# ETHERNET.net
KiCad netlist of a schematic drawn in Altium Designer
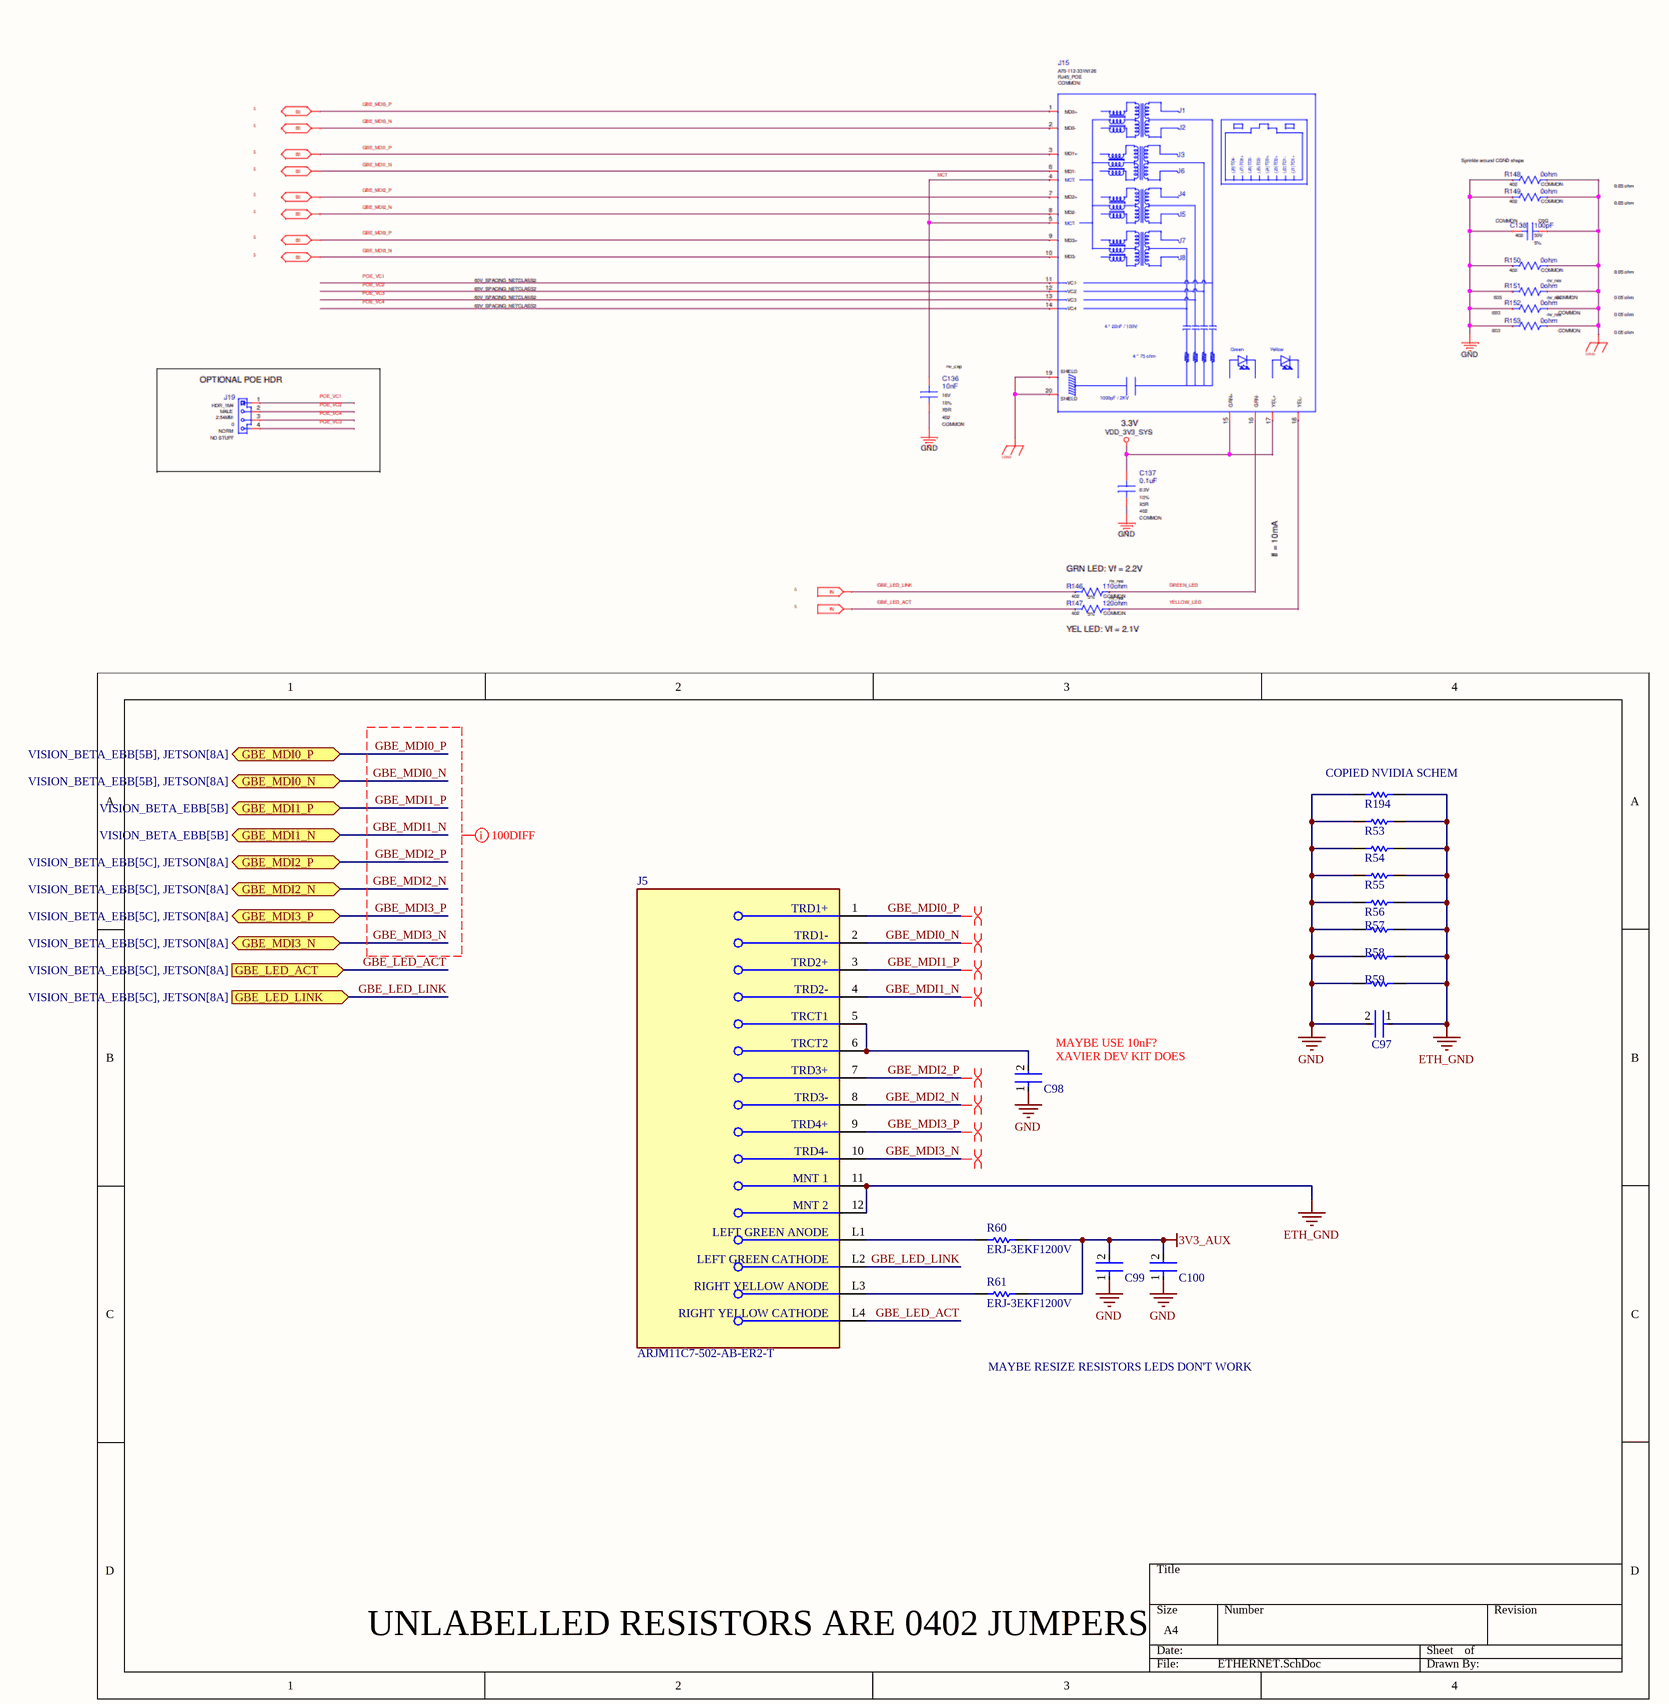
[diagram p0: ETHERNET.SchDoc]

(export (version "E")
  (design (tool "Eeschema 10.0.6"))
  (components
    (comp (ref "C97")
      (value "C1005X7R1H104K050BB")
      (footprint "FP-C1005-050-0_05-IPC_C")
      (description "Multilayer Ceramic Capacitors 100nF ±10% 50V X7R SMD 0402")
      (fields (field (name "VOLTAGE") "50V") (field (name "TOLERANCE") "10%"))
      (libsource (lib "Altium Content Vault") (part "b4654b650e69147ec39a6b967a45e02"))
    )
    (comp (ref "C98")
      (value "C1005X7R1H104K050BB")
      (footprint "FP-C1005-050-0_05-IPC_C")
      (description "Multilayer Ceramic Capacitors 100nF ±10% 50V X7R SMD 0402")
      (fields (field (name "VOLTAGE") "50V") (field (name "TOLERANCE") "10%"))
      (libsource (lib "Altium Content Vault") (part "b4654b650e69147ec39a6b967a45e02"))
    )
    (comp (ref "C99")
      (value "C1005X7R1H104K050BB")
      (footprint "FP-C1005-050-0_05-IPC_C")
      (description "Multilayer Ceramic Capacitors 100nF ±10% 50V X7R SMD 0402")
      (fields (field (name "VOLTAGE") "50V") (field (name "TOLERANCE") "10%"))
      (libsource (lib "Altium Content Vault") (part "b4654b650e69147ec39a6b967a45e02"))
    )
    (comp (ref "C100")
      (value "C1005X7R1H104K050BB")
      (footprint "FP-C1005-050-0_05-IPC_C")
      (description "Multilayer Ceramic Capacitors 100nF ±10% 50V X7R SMD 0402")
      (fields (field (name "VOLTAGE") "50V") (field (name "TOLERANCE") "10%"))
      (libsource (lib "Altium Content Vault") (part "b4654b650e69147ec39a6b967a45e02"))
    )
    (comp (ref "J5")
      (value "ARJM11C7-502-AB-ER2-T")
      (footprint "FP-ARJM11C7-502-AB-ER2-T-MFG")
      (description "RJ45 JACK W/MAG 1X1 1000BASE-T")
      (fields
        (field (name "MANUFACTURER") "Abracon")
        (field (name "OCTOPART") "https://octopart.com/arjm11c7-502-ab-er2-t-abracon-86945316")
      )
      (libsource (lib "Altium Content Vault") (part "c9e9675df30893a1b3e4105448caa83"))
    )
    (comp (ref "R53")
      (value "0402 JUMPER")
      (footprint "RESC1005X40X25ML05T05")
      (description "READ THE NAME")
      (libsource (lib "Space Concordia") (part "CMP-009-00206-2"))
    )
    (comp (ref "R54")
      (value "0402 JUMPER")
      (footprint "RESC1005X40X25ML05T05")
      (description "READ THE NAME")
      (libsource (lib "Space Concordia") (part "CMP-009-00206-2"))
    )
    (comp (ref "R55")
      (value "0402 JUMPER")
      (footprint "RESC1005X40X25ML05T05")
      (description "READ THE NAME")
      (libsource (lib "Space Concordia") (part "CMP-009-00206-2"))
    )
    (comp (ref "R56")
      (value "0402 JUMPER")
      (footprint "RESC1005X40X25ML05T05")
      (description "READ THE NAME")
      (libsource (lib "Space Concordia") (part "CMP-009-00206-2"))
    )
    (comp (ref "R57")
      (value "0402 JUMPER")
      (footprint "RESC1005X40X25ML05T05")
      (description "READ THE NAME")
      (libsource (lib "Space Concordia") (part "CMP-009-00206-2"))
    )
    (comp (ref "R58")
      (value "0402 JUMPER")
      (footprint "RESC1005X40X25ML05T05")
      (description "READ THE NAME")
      (libsource (lib "Space Concordia") (part "CMP-009-00206-2"))
    )
    (comp (ref "R59")
      (value "0402 JUMPER")
      (footprint "RESC1005X40X25ML05T05")
      (description "READ THE NAME")
      (libsource (lib "Space Concordia") (part "CMP-009-00206-2"))
    )
    (comp (ref "R60")
      (value "ERJ-3EKF1200V")
      (footprint "RESC1609X55X30ML15T15")
      (description "Chip Resistor, 120 Ohm, +/- 1%, 0.1 W, -55 to 155 degC, 0603 (1608 Metric), RoHS, Tape and Reel")
      (fields (field (name "TOLERANCE") "1%") (field (name "MANUFACTURER") "Panasonic"))
      (libsource (lib "Altium Content Vault") (part "RES-2"))
    )
    (comp (ref "R61")
      (value "ERJ-3EKF1200V")
      (footprint "RESC1609X55X30ML15T15")
      (description "Chip Resistor, 120 Ohm, +/- 1%, 0.1 W, -55 to 155 degC, 0603 (1608 Metric), RoHS, Tape and Reel")
      (fields (field (name "TOLERANCE") "1%") (field (name "MANUFACTURER") "Panasonic"))
      (libsource (lib "Altium Content Vault") (part "RES-2"))
    )
    (comp (ref "R194")
      (value "0402 JUMPER")
      (footprint "RESC1005X40X25ML05T05")
      (description "READ THE NAME")
      (libsource (lib "Space Concordia") (part "CMP-009-00206-2"))
    )
  )
  (nets
    (net (code "1") (name "/GBE_LED_ACT") (class "Default")
      (node (ref "J5") (pin "L4") (pinfunction "RIGHT_YELLOW_CATHODE_L4") (pintype "passive"))
    )
    (net (code "2") (name "/GBE_LED_LINK") (class "Default")
      (node (ref "J5") (pin "L2") (pinfunction "LEFT_GREEN_CATHODE_L2") (pintype "passive"))
    )
    (net (code "3") (name "/GBE_MDI0_N") (class "Default")
      (node (ref "J5") (pin "2") (pinfunction "TRD1-_2") (pintype "passive"))
    )
    (net (code "4") (name "/GBE_MDI0_P") (class "Default")
      (node (ref "J5") (pin "1") (pinfunction "TRD1+_1") (pintype "passive"))
    )
    (net (code "5") (name "/GBE_MDI1_N") (class "Default")
      (node (ref "J5") (pin "4") (pinfunction "TRD2-_4") (pintype "passive"))
    )
    (net (code "6") (name "/GBE_MDI1_P") (class "Default")
      (node (ref "J5") (pin "3") (pinfunction "TRD2+_3") (pintype "passive"))
    )
    (net (code "7") (name "/GBE_MDI2_N") (class "Default")
      (node (ref "J5") (pin "8") (pinfunction "TRD3-_8") (pintype "passive"))
    )
    (net (code "8") (name "/GBE_MDI2_P") (class "Default")
      (node (ref "J5") (pin "7") (pinfunction "TRD3+_7") (pintype "passive"))
    )
    (net (code "9") (name "/GBE_MDI3_N") (class "Default")
      (node (ref "J5") (pin "10") (pinfunction "TRD4-_10") (pintype "passive"))
    )
    (net (code "10") (name "/GBE_MDI3_P") (class "Default")
      (node (ref "J5") (pin "9") (pinfunction "TRD4+_9") (pintype "passive"))
    )
    (net (code "11") (name "3V3_AUX") (class "Default")
      (node (ref "C100") (pin "2") (pinfunction "2_2") (pintype "passive"))
      (node (ref "C99") (pin "2") (pinfunction "2_2") (pintype "passive"))
      (node (ref "R60") (pin "2") (pinfunction "2_2") (pintype "passive"))
      (node (ref "R61") (pin "2") (pinfunction "2_2") (pintype "passive"))
    )
    (net (code "12") (name "ETH_GND") (class "Default")
      (node (ref "C97") (pin "1") (pinfunction "1_1") (pintype "passive"))
      (node (ref "J5") (pin "11") (pinfunction "MNT_1_11") (pintype "passive"))
      (node (ref "J5") (pin "12") (pinfunction "MNT_2_12") (pintype "passive"))
      (node (ref "R194") (pin "2") (pinfunction "2_2") (pintype "passive"))
      (node (ref "R53") (pin "2") (pinfunction "2_2") (pintype "passive"))
      (node (ref "R54") (pin "2") (pinfunction "2_2") (pintype "passive"))
      (node (ref "R55") (pin "2") (pinfunction "2_2") (pintype "passive"))
      (node (ref "R56") (pin "2") (pinfunction "2_2") (pintype "passive"))
      (node (ref "R57") (pin "2") (pinfunction "2_2") (pintype "passive"))
      (node (ref "R58") (pin "2") (pinfunction "2_2") (pintype "passive"))
      (node (ref "R59") (pin "2") (pinfunction "2_2") (pintype "passive"))
    )
    (net (code "13") (name "GND") (class "Default")
      (node (ref "C100") (pin "1") (pinfunction "1_1") (pintype "passive"))
      (node (ref "C97") (pin "2") (pinfunction "2_2") (pintype "passive"))
      (node (ref "C98") (pin "1") (pinfunction "1_1") (pintype "passive"))
      (node (ref "C99") (pin "1") (pinfunction "1_1") (pintype "passive"))
      (node (ref "R194") (pin "1") (pinfunction "1_1") (pintype "passive"))
      (node (ref "R53") (pin "1") (pinfunction "1_1") (pintype "passive"))
      (node (ref "R54") (pin "1") (pinfunction "1_1") (pintype "passive"))
      (node (ref "R55") (pin "1") (pinfunction "1_1") (pintype "passive"))
      (node (ref "R56") (pin "1") (pinfunction "1_1") (pintype "passive"))
      (node (ref "R57") (pin "1") (pinfunction "1_1") (pintype "passive"))
      (node (ref "R58") (pin "1") (pinfunction "1_1") (pintype "passive"))
      (node (ref "R59") (pin "1") (pinfunction "1_1") (pintype "passive"))
    )
    (net (code "14") (name "Net-(J5-LEFT_GREEN_ANODE)") (class "Default")
      (node (ref "J5") (pin "L1") (pinfunction "LEFT_GREEN_ANODE_L1") (pintype "passive"))
      (node (ref "R60") (pin "1") (pinfunction "1_1") (pintype "passive"))
    )
    (net (code "15") (name "Net-(J5-RIGHT_YELLOW_ANODE)") (class "Default")
      (node (ref "J5") (pin "L3") (pinfunction "RIGHT_YELLOW_ANODE_L3") (pintype "passive"))
      (node (ref "R61") (pin "1") (pinfunction "1_1") (pintype "passive"))
    )
    (net (code "16") (name "Net-(J5-TRCT1)") (class "Default")
      (node (ref "C98") (pin "2") (pinfunction "2_2") (pintype "passive"))
      (node (ref "J5") (pin "5") (pinfunction "TRCT1_5") (pintype "passive"))
      (node (ref "J5") (pin "6") (pinfunction "TRCT2_6") (pintype "passive"))
    )
  )
)
